# Qwiic_Quad_Relay.net
KiCad netlist of a schematic drawn in EAGLE
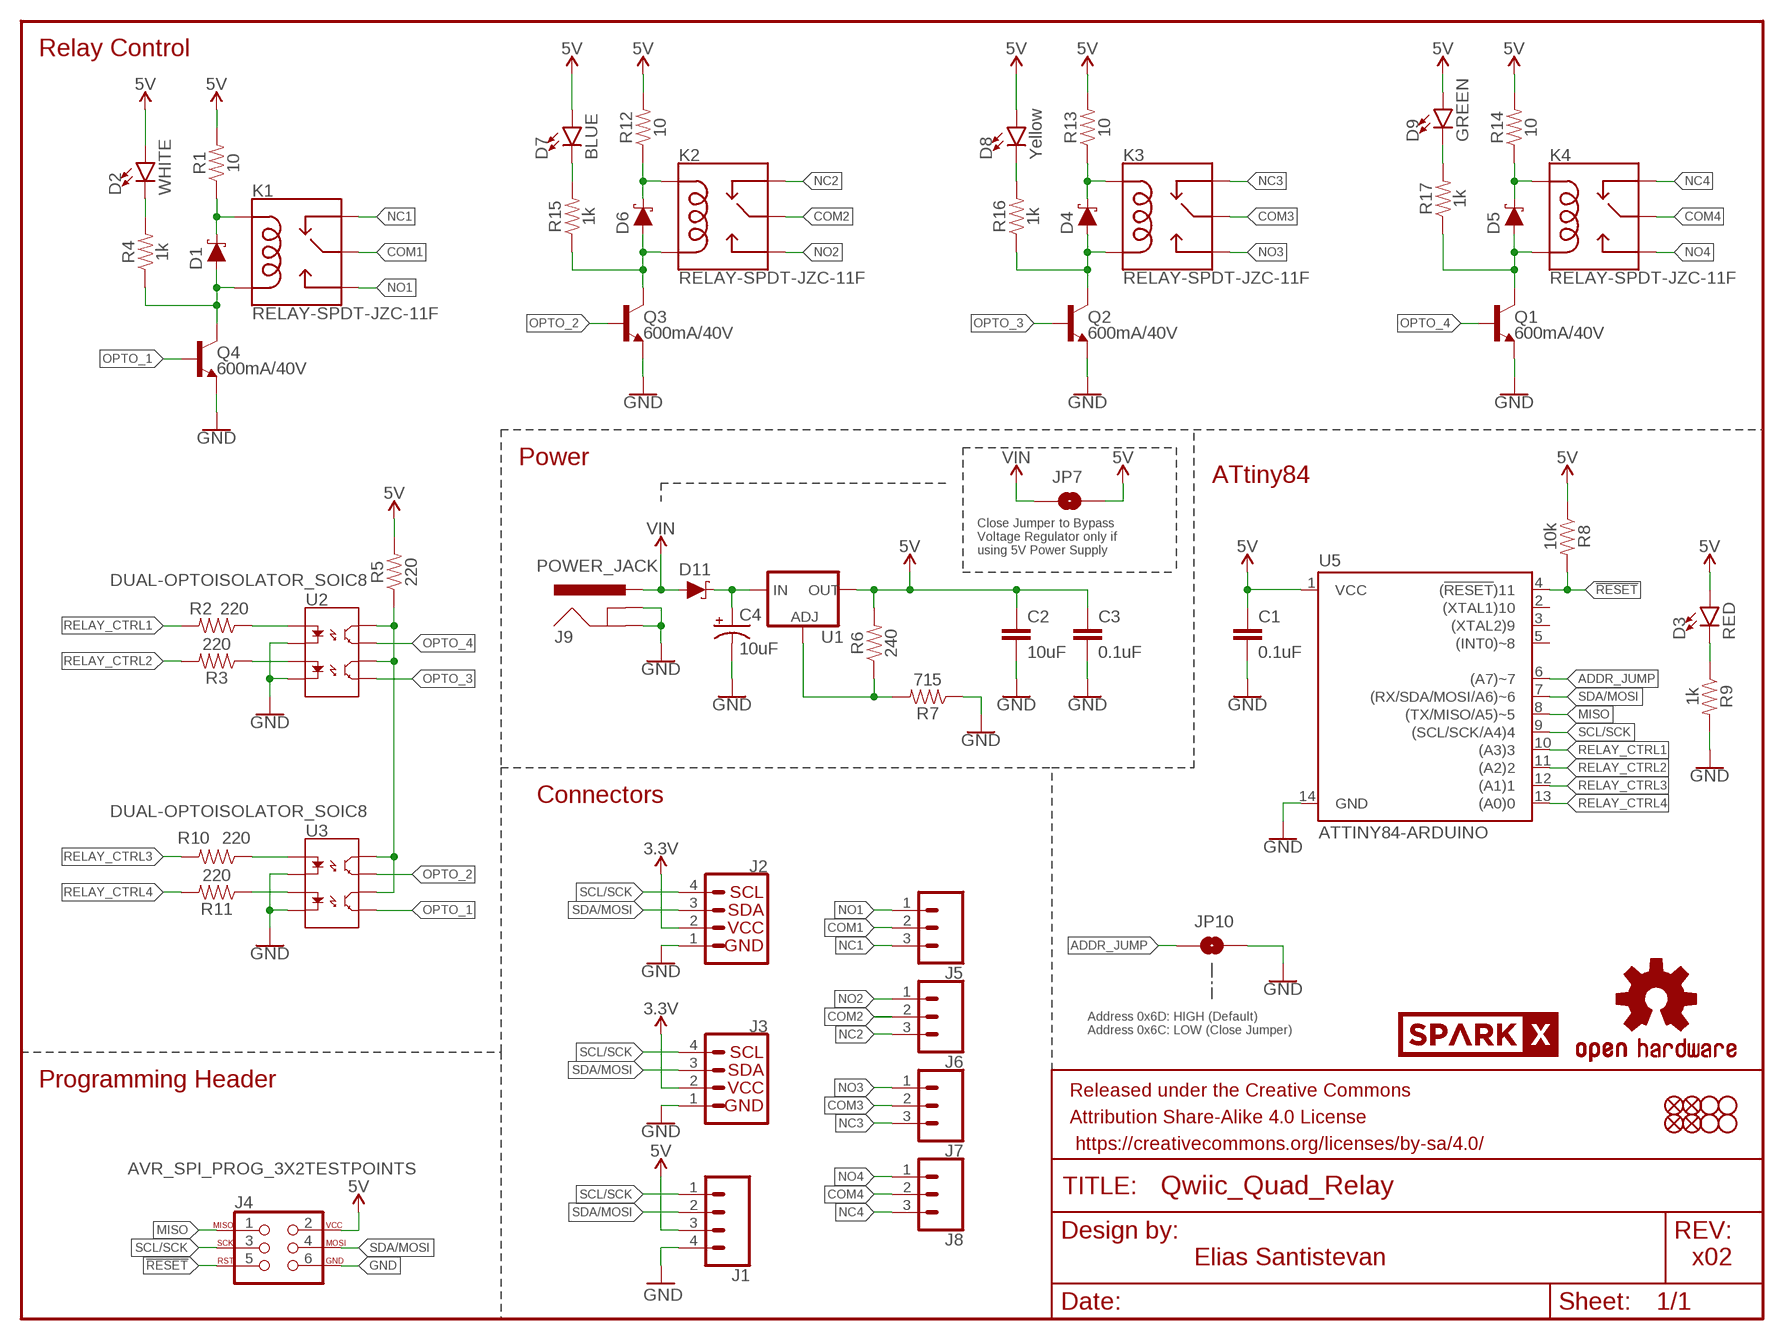
[diagram p0: schematic, sheet 1]

(export (version "E")
  (design (tool "Eeschema 10.0.6"))
  (components
    (comp (ref "C1")
      (value "0.1uF")
      (footprint "eagle-import:0603")
      (libsource (lib "eagle-import") (part "0.1UF-0603-25V-(+80/-20%)"))
    )
    (comp (ref "C2")
      (value "10uF")
      (footprint "eagle-import:0603")
      (libsource (lib "eagle-import") (part "10UF-0603-6.3V-20%"))
    )
    (comp (ref "C3")
      (value "0.1uF")
      (footprint "eagle-import:0603")
      (libsource (lib "eagle-import") (part "0.1UF-0603-25V-(+80/-20%)"))
    )
    (comp (ref "C4")
      (value "10uF")
      (footprint "eagle-import:EIA3528")
      (libsource (lib "eagle-import") (part "10UF-POLAR-EIA3528-20V-10%(TANT)"))
    )
    (comp (ref "D1")
      (value "1A/23V/620mV")
      (footprint "eagle-import:SOD-323")
      (libsource (lib "eagle-import") (part "DIODE-SCHOTTKY-BAT20J"))
    )
    (comp (ref "D2")
      (value "WHITE")
      (footprint "eagle-import:LED-0603")
      (libsource (lib "eagle-import") (part "LED-WHITE0603"))
    )
    (comp (ref "D3")
      (value "RED")
      (footprint "eagle-import:LED-0603")
      (libsource (lib "eagle-import") (part "LED-RED0603"))
    )
    (comp (ref "D4")
      (value "1A/23V/620mV")
      (footprint "eagle-import:SOD-323")
      (libsource (lib "eagle-import") (part "DIODE-SCHOTTKY-BAT20J"))
    )
    (comp (ref "D5")
      (value "1A/23V/620mV")
      (footprint "eagle-import:SOD-323")
      (libsource (lib "eagle-import") (part "DIODE-SCHOTTKY-BAT20J"))
    )
    (comp (ref "D6")
      (value "1A/23V/620mV")
      (footprint "eagle-import:SOD-323")
      (libsource (lib "eagle-import") (part "DIODE-SCHOTTKY-BAT20J"))
    )
    (comp (ref "D7")
      (value "BLUE")
      (footprint "eagle-import:LED-0603")
      (libsource (lib "eagle-import") (part "LED-BLUE0603"))
    )
    (comp (ref "D8")
      (value "Yellow")
      (footprint "eagle-import:LED-0603")
      (libsource (lib "eagle-import") (part "LED-YELLOW0603"))
    )
    (comp (ref "D9")
      (value "GREEN")
      (footprint "eagle-import:LED-0603")
      (libsource (lib "eagle-import") (part "LED-GREEN0603"))
    )
    (comp (ref "D11")
      (value "1A/40V/500mV")
      (footprint "eagle-import:SMA-DIODE")
      (libsource (lib "eagle-import") (part "DIODE-SCHOTTKY-SS14"))
    )
    (comp (ref "FRAME1")
      (value "FRAME-LETTER")
      (footprint "eagle-import:CREATIVE_COMMONS")
      (libsource (lib "eagle-import") (part "FRAME-LETTER"))
    )
    (comp (ref "J1")
      (value "CONN_041X04_NO_SILK")
      (footprint "eagle-import:1X04_NO_SILK")
      (libsource (lib "eagle-import") (part "CONN_041X04_NO_SILK"))
    )
    (comp (ref "J2")
      (value "Qwiic Right Angle")
      (footprint "eagle-import:1X04_1MM_RA")
      (libsource (lib "eagle-import") (part "I2C_STANDARDQWIIC"))
    )
    (comp (ref "J3")
      (value "Qwiic Right Angle")
      (footprint "eagle-import:1X04_1MM_RA")
      (libsource (lib "eagle-import") (part "I2C_STANDARDQWIIC"))
    )
    (comp (ref "J4")
      (value "AVR_SPI_PROG_3X2TESTPOINTS")
      (footprint "eagle-import:2X3_TEST_POINTS")
      (libsource (lib "eagle-import") (part "AVR_SPI_PROG_3X2TESTPOINTS"))
    )
    (comp (ref "J5")
      (value "CONN_03-SCREW-5MM")
      (footprint "eagle-import:SCREWTERMINAL-5MM-3")
      (libsource (lib "eagle-import") (part "CONN_03-SCREW-5MM"))
    )
    (comp (ref "J6")
      (value "CONN_03-SCREW-5MM")
      (footprint "eagle-import:SCREWTERMINAL-5MM-3")
      (libsource (lib "eagle-import") (part "CONN_03-SCREW-5MM"))
    )
    (comp (ref "J7")
      (value "CONN_03-SCREW-5MM")
      (footprint "eagle-import:SCREWTERMINAL-5MM-3")
      (libsource (lib "eagle-import") (part "CONN_03-SCREW-5MM"))
    )
    (comp (ref "J8")
      (value "CONN_03-SCREW-5MM")
      (footprint "eagle-import:SCREWTERMINAL-5MM-3")
      (libsource (lib "eagle-import") (part "CONN_03-SCREW-5MM"))
    )
    (comp (ref "J9")
      (value "POWER_JACK")
      (footprint "eagle-import:POWER_JACK_PTH")
      (libsource (lib "eagle-import") (part "POWER_JACK"))
    )
    (comp (ref "JP1")
      (value "STAND-OFF")
      (footprint "eagle-import:STAND-OFF")
      (libsource (lib "eagle-import") (part "STAND-OFF"))
    )
    (comp (ref "JP2")
      (value "FIDUCIAL1X2")
      (footprint "eagle-import:FIDUCIAL-1X2")
      (libsource (lib "eagle-import") (part "FIDUCIAL1X2"))
    )
    (comp (ref "JP3")
      (value "STAND-OFF")
      (footprint "eagle-import:STAND-OFF")
      (libsource (lib "eagle-import") (part "STAND-OFF"))
    )
    (comp (ref "JP4")
      (value "STAND-OFF")
      (footprint "eagle-import:STAND-OFF")
      (libsource (lib "eagle-import") (part "STAND-OFF"))
    )
    (comp (ref "JP5")
      (value "STAND-OFF")
      (footprint "eagle-import:STAND-OFF")
      (libsource (lib "eagle-import") (part "STAND-OFF"))
    )
    (comp (ref "JP6")
      (value "FIDUCIAL1X2")
      (footprint "eagle-import:FIDUCIAL-1X2")
      (libsource (lib "eagle-import") (part "FIDUCIAL1X2"))
    )
    (comp (ref "JP7")
      (value "JUMPER-SMT_2_NO_SILK")
      (footprint "eagle-import:SMT-JUMPER_2_NO_SILK")
      (libsource (lib "eagle-import") (part "JUMPER-SMT_2_NO_SILK"))
    )
    (comp (ref "JP8")
      (value "FIDUCIAL1X2")
      (footprint "eagle-import:FIDUCIAL-1X2")
      (libsource (lib "eagle-import") (part "FIDUCIAL1X2"))
    )
    (comp (ref "JP9")
      (value "FIDUCIAL1X2")
      (footprint "eagle-import:FIDUCIAL-1X2")
      (libsource (lib "eagle-import") (part "FIDUCIAL1X2"))
    )
    (comp (ref "JP10")
      (value "JUMPER-SMT_2_NO_SILK")
      (footprint "eagle-import:SMT-JUMPER_2_NO_SILK")
      (libsource (lib "eagle-import") (part "JUMPER-SMT_2_NO_SILK"))
    )
    (comp (ref "K1")
      (value "RELAY-SPDT-JZC-11F")
      (footprint "eagle-import:RELAY-JZC")
      (libsource (lib "eagle-import") (part "RELAY-SPDT-JZC-11F"))
    )
    (comp (ref "K2")
      (value "RELAY-SPDT-JZC-11F")
      (footprint "eagle-import:RELAY-JZC")
      (libsource (lib "eagle-import") (part "RELAY-SPDT-JZC-11F"))
    )
    (comp (ref "K3")
      (value "RELAY-SPDT-JZC-11F")
      (footprint "eagle-import:RELAY-JZC")
      (libsource (lib "eagle-import") (part "RELAY-SPDT-JZC-11F"))
    )
    (comp (ref "K4")
      (value "RELAY-SPDT-JZC-11F")
      (footprint "eagle-import:RELAY-JZC")
      (libsource (lib "eagle-import") (part "RELAY-SPDT-JZC-11F"))
    )
    (comp (ref "LOGO1")
      (value "OSHW-LOGOS")
      (footprint "eagle-import:OSHW-LOGO-S")
      (libsource (lib "eagle-import") (part "OSHW-LOGOS"))
    )
    (comp (ref "Q1")
      (value "600mA/40V")
      (footprint "eagle-import:SOT23-3")
      (libsource (lib "eagle-import") (part "TRANS_NPN-MMBT2222AL"))
    )
    (comp (ref "Q2")
      (value "600mA/40V")
      (footprint "eagle-import:SOT23-3")
      (libsource (lib "eagle-import") (part "TRANS_NPN-MMBT2222AL"))
    )
    (comp (ref "Q3")
      (value "600mA/40V")
      (footprint "eagle-import:SOT23-3")
      (libsource (lib "eagle-import") (part "TRANS_NPN-MMBT2222AL"))
    )
    (comp (ref "Q4")
      (value "600mA/40V")
      (footprint "eagle-import:SOT23-3")
      (libsource (lib "eagle-import") (part "TRANS_NPN-MMBT2222AL"))
    )
    (comp (ref "R1")
      (value "10")
      (footprint "eagle-import:0603")
      (libsource (lib "eagle-import") (part "10OHM-0603-1/10W-5%"))
    )
    (comp (ref "R2")
      (value "220")
      (footprint "eagle-import:0603")
      (libsource (lib "eagle-import") (part "220OHM-0603-1/10W-1%"))
    )
    (comp (ref "R3")
      (value "220")
      (footprint "eagle-import:0603")
      (libsource (lib "eagle-import") (part "220OHM-0603-1/10W-1%"))
    )
    (comp (ref "R4")
      (value "1k")
      (footprint "eagle-import:0603")
      (libsource (lib "eagle-import") (part "1KOHM-0603-1/10W-1%"))
    )
    (comp (ref "R5")
      (value "220")
      (footprint "eagle-import:0603")
      (libsource (lib "eagle-import") (part "220OHM-0603-1/10W-1%"))
    )
    (comp (ref "R6")
      (value "240")
      (footprint "eagle-import:0603")
      (libsource (lib "eagle-import") (part "240OHM-0603-1/10W-1%"))
    )
    (comp (ref "R7")
      (value "715")
      (footprint "eagle-import:0603")
      (libsource (lib "eagle-import") (part "715OHM-0603-1/10W-1%"))
    )
    (comp (ref "R8")
      (value "10k")
      (footprint "eagle-import:0603")
      (libsource (lib "eagle-import") (part "10KOHM-0603-1/10W-1%"))
    )
    (comp (ref "R9")
      (value "1k")
      (footprint "eagle-import:0603")
      (libsource (lib "eagle-import") (part "1KOHM-0603-1/10W-1%"))
    )
    (comp (ref "R10")
      (value "220")
      (footprint "eagle-import:0603")
      (libsource (lib "eagle-import") (part "220OHM-0603-1/10W-1%"))
    )
    (comp (ref "R11")
      (value "220")
      (footprint "eagle-import:0603")
      (libsource (lib "eagle-import") (part "220OHM-0603-1/10W-1%"))
    )
    (comp (ref "R12")
      (value "10")
      (footprint "eagle-import:0603")
      (libsource (lib "eagle-import") (part "10OHM-0603-1/10W-5%"))
    )
    (comp (ref "R13")
      (value "10")
      (footprint "eagle-import:0603")
      (libsource (lib "eagle-import") (part "10OHM-0603-1/10W-5%"))
    )
    (comp (ref "R14")
      (value "10")
      (footprint "eagle-import:0603")
      (libsource (lib "eagle-import") (part "10OHM-0603-1/10W-5%"))
    )
    (comp (ref "R15")
      (value "1k")
      (footprint "eagle-import:0603")
      (libsource (lib "eagle-import") (part "1KOHM-0603-1/10W-1%"))
    )
    (comp (ref "R16")
      (value "1k")
      (footprint "eagle-import:0603")
      (libsource (lib "eagle-import") (part "1KOHM-0603-1/10W-1%"))
    )
    (comp (ref "R17")
      (value "1k")
      (footprint "eagle-import:0603")
      (libsource (lib "eagle-import") (part "1KOHM-0603-1/10W-1%"))
    )
    (comp (ref "U$12")
      (value "SPARKX-LOGO4")
      (footprint "eagle-import:SPARKX-MEDIUM")
      (libsource (lib "eagle-import") (part "SPARKX-LOGO4"))
    )
    (comp (ref "U1")
      (value "V_REG_LM1117SOT223")
      (footprint "eagle-import:SOT223")
      (libsource (lib "eagle-import") (part "V_REG_LM1117SOT223"))
    )
    (comp (ref "U2")
      (value "DUAL-OPTOISOLATOR_SOIC8")
      (footprint "eagle-import:SO08")
      (libsource (lib "eagle-import") (part "DUAL-OPTOISOLATOR_SOIC8"))
    )
    (comp (ref "U3")
      (value "DUAL-OPTOISOLATOR_SOIC8")
      (footprint "eagle-import:SO08")
      (libsource (lib "eagle-import") (part "DUAL-OPTOISOLATOR_SOIC8"))
    )
    (comp (ref "U5")
      (value "ATTINY84-ARDUINO")
      (footprint "eagle-import:SO14")
      (libsource (lib "eagle-import") (part "ATTINY84-ARDUINO"))
    )
  )
  (nets
    (net (code "1") (name "/~{RESET}") (class "Default")
      (node (ref "J4") (pin "5") (pinfunction "5_5") (pintype "passive"))
      (node (ref "R8") (pin "2") (pinfunction "2_2") (pintype "passive"))
      (node (ref "U5") (pin "4") (pinfunction "(~{RESET})11_4") (pintype "bidirectional"))
    )
    (net (code "2") (name "3.3V") (class "Default")
      (node (ref "J2") (pin "2") (pinfunction "2_2") (pintype "power_in"))
      (node (ref "J3") (pin "2") (pinfunction "2_2") (pintype "power_in"))
    )
    (net (code "3") (name "5V") (class "Default")
      (node (ref "C1") (pin "1") (pinfunction "1_1") (pintype "passive"))
      (node (ref "C2") (pin "1") (pinfunction "1_1") (pintype "passive"))
      (node (ref "C3") (pin "1") (pinfunction "1_1") (pintype "passive"))
      (node (ref "D2") (pin "A") (pinfunction "A_A") (pintype "passive"))
      (node (ref "D3") (pin "A") (pinfunction "A_A") (pintype "passive"))
      (node (ref "D7") (pin "A") (pinfunction "A_A") (pintype "passive"))
      (node (ref "D8") (pin "A") (pinfunction "A_A") (pintype "passive"))
      (node (ref "D9") (pin "A") (pinfunction "A_A") (pintype "passive"))
      (node (ref "J1") (pin "3") (pinfunction "3_3") (pintype "passive"))
      (node (ref "J4") (pin "2") (pinfunction "2_2") (pintype "passive"))
      (node (ref "JP7") (pin "2") (pinfunction "2_2") (pintype "passive"))
      (node (ref "R1") (pin "2") (pinfunction "2_2") (pintype "passive"))
      (node (ref "R12") (pin "2") (pinfunction "2_2") (pintype "passive"))
      (node (ref "R13") (pin "2") (pinfunction "2_2") (pintype "passive"))
      (node (ref "R14") (pin "2") (pinfunction "2_2") (pintype "passive"))
      (node (ref "R5") (pin "2") (pinfunction "2_2") (pintype "passive"))
      (node (ref "R6") (pin "2") (pinfunction "2_2") (pintype "passive"))
      (node (ref "R8") (pin "1") (pinfunction "1_1") (pintype "passive"))
      (node (ref "U1") (pin "2") (pinfunction "OUT_2") (pintype "output"))
      (node (ref "U1") (pin "4") (pinfunction "OUT_4") (pintype "output"))
      (node (ref "U5") (pin "1") (pinfunction "VCC_1") (pintype "bidirectional"))
    )
    (net (code "4") (name "ADDR_JUMP") (class "Default")
      (node (ref "JP10") (pin "1") (pinfunction "1_1") (pintype "passive"))
      (node (ref "U5") (pin "6") (pinfunction "(A7)~{7}_6") (pintype "bidirectional"))
    )
    (net (code "5") (name "COM1") (class "Default")
      (node (ref "J5") (pin "2") (pinfunction "2_2") (pintype "passive"))
      (node (ref "K1") (pin "4") (pinfunction "MAIN_4") (pintype "bidirectional"))
    )
    (net (code "6") (name "COM2") (class "Default")
      (node (ref "J6") (pin "2") (pinfunction "2_2") (pintype "passive"))
      (node (ref "K2") (pin "4") (pinfunction "MAIN_4") (pintype "bidirectional"))
    )
    (net (code "7") (name "COM3") (class "Default")
      (node (ref "J7") (pin "2") (pinfunction "2_2") (pintype "passive"))
      (node (ref "K3") (pin "4") (pinfunction "MAIN_4") (pintype "bidirectional"))
    )
    (net (code "8") (name "COM4") (class "Default")
      (node (ref "J8") (pin "2") (pinfunction "2_2") (pintype "passive"))
      (node (ref "K4") (pin "4") (pinfunction "MAIN_4") (pintype "bidirectional"))
    )
    (net (code "9") (name "GND") (class "Default")
      (node (ref "C1") (pin "2") (pinfunction "2_2") (pintype "passive"))
      (node (ref "C2") (pin "2") (pinfunction "2_2") (pintype "passive"))
      (node (ref "C3") (pin "2") (pinfunction "2_2") (pintype "passive"))
      (node (ref "C4") (pin "C") (pinfunction "-_C") (pintype "passive"))
      (node (ref "J1") (pin "4") (pinfunction "4_4") (pintype "passive"))
      (node (ref "J2") (pin "1") (pinfunction "1_1") (pintype "power_in"))
      (node (ref "J3") (pin "1") (pinfunction "1_1") (pintype "power_in"))
      (node (ref "J4") (pin "6") (pinfunction "6_6") (pintype "passive"))
      (node (ref "J9") (pin "GND") (pinfunction "GND_GND") (pintype "bidirectional"))
      (node (ref "J9") (pin "GNDBREAK") (pinfunction "GNDBREAK_GNDBREAK") (pintype "bidirectional"))
      (node (ref "JP10") (pin "2") (pinfunction "2_2") (pintype "passive"))
      (node (ref "Q1") (pin "2") (pinfunction "E_2") (pintype "passive"))
      (node (ref "Q2") (pin "2") (pinfunction "E_2") (pintype "passive"))
      (node (ref "Q3") (pin "2") (pinfunction "E_2") (pintype "passive"))
      (node (ref "Q4") (pin "2") (pinfunction "E_2") (pintype "passive"))
      (node (ref "R7") (pin "1") (pinfunction "1_1") (pintype "passive"))
      (node (ref "R9") (pin "2") (pinfunction "2_2") (pintype "passive"))
      (node (ref "U2") (pin "2") (pinfunction "C1_2") (pintype "bidirectional"))
      (node (ref "U2") (pin "4") (pinfunction "C2_4") (pintype "bidirectional"))
      (node (ref "U3") (pin "2") (pinfunction "C1_2") (pintype "bidirectional"))
      (node (ref "U3") (pin "4") (pinfunction "C2_4") (pintype "bidirectional"))
      (node (ref "U5") (pin "14") (pinfunction "GND_14") (pintype "bidirectional"))
    )
    (net (code "10") (name "MISO") (class "Default")
      (node (ref "J4") (pin "1") (pinfunction "1_1") (pintype "passive"))
      (node (ref "U5") (pin "8") (pinfunction "(TX/MISO/A5)~{5}_8") (pintype "bidirectional"))
    )
    (net (code "11") (name "NC1") (class "Default")
      (node (ref "J5") (pin "3") (pinfunction "3_3") (pintype "passive"))
      (node (ref "K1") (pin "2") (pinfunction "NC_2") (pintype "bidirectional"))
    )
    (net (code "12") (name "NC2") (class "Default")
      (node (ref "J6") (pin "3") (pinfunction "3_3") (pintype "passive"))
      (node (ref "K2") (pin "2") (pinfunction "NC_2") (pintype "bidirectional"))
    )
    (net (code "13") (name "NC3") (class "Default")
      (node (ref "J7") (pin "3") (pinfunction "3_3") (pintype "passive"))
      (node (ref "K3") (pin "2") (pinfunction "NC_2") (pintype "bidirectional"))
    )
    (net (code "14") (name "NC4") (class "Default")
      (node (ref "J8") (pin "3") (pinfunction "3_3") (pintype "passive"))
      (node (ref "K4") (pin "2") (pinfunction "NC_2") (pintype "bidirectional"))
    )
    (net (code "15") (name "NO1") (class "Default")
      (node (ref "J5") (pin "1") (pinfunction "1_1") (pintype "passive"))
      (node (ref "K1") (pin "3") (pinfunction "NO_3") (pintype "bidirectional"))
    )
    (net (code "16") (name "NO2") (class "Default")
      (node (ref "J6") (pin "1") (pinfunction "1_1") (pintype "passive"))
      (node (ref "K2") (pin "3") (pinfunction "NO_3") (pintype "bidirectional"))
    )
    (net (code "17") (name "NO3") (class "Default")
      (node (ref "J7") (pin "1") (pinfunction "1_1") (pintype "passive"))
      (node (ref "K3") (pin "3") (pinfunction "NO_3") (pintype "bidirectional"))
    )
    (net (code "18") (name "NO4") (class "Default")
      (node (ref "J8") (pin "1") (pinfunction "1_1") (pintype "passive"))
      (node (ref "K4") (pin "3") (pinfunction "NO_3") (pintype "bidirectional"))
    )
    (net (code "19") (name "Net-(C4-+)") (class "Default")
      (node (ref "C4") (pin "A") (pinfunction "+_A") (pintype "passive"))
      (node (ref "D11") (pin "C") (pinfunction "C_C") (pintype "passive"))
      (node (ref "U1") (pin "3") (pinfunction "IN_3") (pintype "input"))
    )
    (net (code "20") (name "Net-(D2-PadC)") (class "Default")
      (node (ref "D2") (pin "C") (pinfunction "C_C") (pintype "passive"))
      (node (ref "R4") (pin "2") (pinfunction "2_2") (pintype "passive"))
    )
    (net (code "21") (name "Net-(D3-PadC)") (class "Default")
      (node (ref "D3") (pin "C") (pinfunction "C_C") (pintype "passive"))
      (node (ref "R9") (pin "1") (pinfunction "1_1") (pintype "passive"))
    )
    (net (code "22") (name "Net-(D7-PadC)") (class "Default")
      (node (ref "D7") (pin "C") (pinfunction "C_C") (pintype "passive"))
      (node (ref "R15") (pin "2") (pinfunction "2_2") (pintype "passive"))
    )
    (net (code "23") (name "Net-(D8-PadC)") (class "Default")
      (node (ref "D8") (pin "C") (pinfunction "C_C") (pintype "passive"))
      (node (ref "R16") (pin "2") (pinfunction "2_2") (pintype "passive"))
    )
    (net (code "24") (name "Net-(D9-PadC)") (class "Default")
      (node (ref "D9") (pin "C") (pinfunction "C_C") (pintype "passive"))
      (node (ref "R17") (pin "2") (pinfunction "2_2") (pintype "passive"))
    )
    (net (code "25") (name "Net-(K1-COIL1)") (class "Default")
      (node (ref "D1") (pin "C") (pinfunction "C_C") (pintype "passive"))
      (node (ref "K1") (pin "5") (pinfunction "COIL1_5") (pintype "bidirectional"))
      (node (ref "R1") (pin "1") (pinfunction "1_1") (pintype "passive"))
    )
    (net (code "26") (name "Net-(K1-COIL2)") (class "Default")
      (node (ref "D1") (pin "A") (pinfunction "A_A") (pintype "passive"))
      (node (ref "K1") (pin "1") (pinfunction "COIL2_1") (pintype "bidirectional"))
      (node (ref "Q4") (pin "3") (pinfunction "C_3") (pintype "passive"))
      (node (ref "R4") (pin "1") (pinfunction "1_1") (pintype "passive"))
    )
    (net (code "27") (name "Net-(K2-COIL1)") (class "Default")
      (node (ref "D6") (pin "C") (pinfunction "C_C") (pintype "passive"))
      (node (ref "K2") (pin "5") (pinfunction "COIL1_5") (pintype "bidirectional"))
      (node (ref "R12") (pin "1") (pinfunction "1_1") (pintype "passive"))
    )
    (net (code "28") (name "Net-(K2-COIL2)") (class "Default")
      (node (ref "D6") (pin "A") (pinfunction "A_A") (pintype "passive"))
      (node (ref "K2") (pin "1") (pinfunction "COIL2_1") (pintype "bidirectional"))
      (node (ref "Q3") (pin "3") (pinfunction "C_3") (pintype "passive"))
      (node (ref "R15") (pin "1") (pinfunction "1_1") (pintype "passive"))
    )
    (net (code "29") (name "Net-(K3-COIL1)") (class "Default")
      (node (ref "D4") (pin "C") (pinfunction "C_C") (pintype "passive"))
      (node (ref "K3") (pin "5") (pinfunction "COIL1_5") (pintype "bidirectional"))
      (node (ref "R13") (pin "1") (pinfunction "1_1") (pintype "passive"))
    )
    (net (code "30") (name "Net-(K3-COIL2)") (class "Default")
      (node (ref "D4") (pin "A") (pinfunction "A_A") (pintype "passive"))
      (node (ref "K3") (pin "1") (pinfunction "COIL2_1") (pintype "bidirectional"))
      (node (ref "Q2") (pin "3") (pinfunction "C_3") (pintype "passive"))
      (node (ref "R16") (pin "1") (pinfunction "1_1") (pintype "passive"))
    )
    (net (code "31") (name "Net-(K4-COIL1)") (class "Default")
      (node (ref "D5") (pin "C") (pinfunction "C_C") (pintype "passive"))
      (node (ref "K4") (pin "5") (pinfunction "COIL1_5") (pintype "bidirectional"))
      (node (ref "R14") (pin "1") (pinfunction "1_1") (pintype "passive"))
    )
    (net (code "32") (name "Net-(K4-COIL2)") (class "Default")
      (node (ref "D5") (pin "A") (pinfunction "A_A") (pintype "passive"))
      (node (ref "K4") (pin "1") (pinfunction "COIL2_1") (pintype "bidirectional"))
      (node (ref "Q1") (pin "3") (pinfunction "C_3") (pintype "passive"))
      (node (ref "R17") (pin "1") (pinfunction "1_1") (pintype "passive"))
    )
    (net (code "33") (name "Net-(U1-ADJ)") (class "Default")
      (node (ref "R6") (pin "1") (pinfunction "1_1") (pintype "passive"))
      (node (ref "R7") (pin "2") (pinfunction "2_2") (pintype "passive"))
      (node (ref "U1") (pin "1") (pinfunction "ADJ_1") (pintype "input"))
    )
    (net (code "34") (name "Net-(U2-A1)") (class "Default")
      (node (ref "R2") (pin "1") (pinfunction "1_1") (pintype "passive"))
      (node (ref "U2") (pin "1") (pinfunction "A1_1") (pintype "bidirectional"))
    )
    (net (code "35") (name "Net-(U2-A2)") (class "Default")
      (node (ref "R3") (pin "1") (pinfunction "1_1") (pintype "passive"))
      (node (ref "U2") (pin "3") (pinfunction "A2_3") (pintype "bidirectional"))
    )
    (net (code "36") (name "Net-(U2-CL1)") (class "Default")
      (node (ref "R5") (pin "1") (pinfunction "1_1") (pintype "passive"))
      (node (ref "U2") (pin "6") (pinfunction "CL2_6") (pintype "bidirectional"))
      (node (ref "U2") (pin "8") (pinfunction "CL1_8") (pintype "bidirectional"))
      (node (ref "U3") (pin "6") (pinfunction "CL2_6") (pintype "bidirectional"))
      (node (ref "U3") (pin "8") (pinfunction "CL1_8") (pintype "bidirectional"))
    )
    (net (code "37") (name "Net-(U3-A1)") (class "Default")
      (node (ref "R10") (pin "1") (pinfunction "1_1") (pintype "passive"))
      (node (ref "U3") (pin "1") (pinfunction "A1_1") (pintype "bidirectional"))
    )
    (net (code "38") (name "Net-(U3-A2)") (class "Default")
      (node (ref "R11") (pin "1") (pinfunction "1_1") (pintype "passive"))
      (node (ref "U3") (pin "3") (pinfunction "A2_3") (pintype "bidirectional"))
    )
    (net (code "39") (name "OPTO_1") (class "Default")
      (node (ref "Q4") (pin "1") (pinfunction "B_1") (pintype "passive"))
      (node (ref "U3") (pin "5") (pinfunction "EM2_5") (pintype "bidirectional"))
    )
    (net (code "40") (name "OPTO_2") (class "Default")
      (node (ref "Q3") (pin "1") (pinfunction "B_1") (pintype "passive"))
      (node (ref "U3") (pin "7") (pinfunction "EM1_7") (pintype "bidirectional"))
    )
    (net (code "41") (name "OPTO_3") (class "Default")
      (node (ref "Q2") (pin "1") (pinfunction "B_1") (pintype "passive"))
      (node (ref "U2") (pin "5") (pinfunction "EM2_5") (pintype "bidirectional"))
    )
    (net (code "42") (name "OPTO_4") (class "Default")
      (node (ref "Q1") (pin "1") (pinfunction "B_1") (pintype "passive"))
      (node (ref "U2") (pin "7") (pinfunction "EM1_7") (pintype "bidirectional"))
    )
    (net (code "43") (name "RELAY_CTRL1") (class "Default")
      (node (ref "R2") (pin "2") (pinfunction "2_2") (pintype "passive"))
      (node (ref "U5") (pin "10") (pinfunction "(A3)3_10") (pintype "bidirectional"))
    )
    (net (code "44") (name "RELAY_CTRL2") (class "Default")
      (node (ref "R3") (pin "2") (pinfunction "2_2") (pintype "passive"))
      (node (ref "U5") (pin "11") (pinfunction "(A2)2_11") (pintype "bidirectional"))
    )
    (net (code "45") (name "RELAY_CTRL3") (class "Default")
      (node (ref "R10") (pin "2") (pinfunction "2_2") (pintype "passive"))
      (node (ref "U5") (pin "12") (pinfunction "(A1)1_12") (pintype "bidirectional"))
    )
    (net (code "46") (name "RELAY_CTRL4") (class "Default")
      (node (ref "R11") (pin "2") (pinfunction "2_2") (pintype "passive"))
      (node (ref "U5") (pin "13") (pinfunction "(A0)0_13") (pintype "bidirectional"))
    )
    (net (code "47") (name "SCL{slash}SCK") (class "Default")
      (node (ref "J1") (pin "1") (pinfunction "1_1") (pintype "passive"))
      (node (ref "J2") (pin "4") (pinfunction "4_4") (pintype "passive"))
      (node (ref "J3") (pin "4") (pinfunction "4_4") (pintype "passive"))
      (node (ref "J4") (pin "3") (pinfunction "3_3") (pintype "passive"))
      (node (ref "U5") (pin "9") (pinfunction "(SCL/SCK/A4)4_9") (pintype "bidirectional"))
    )
    (net (code "48") (name "SDA{slash}MOSI") (class "Default")
      (node (ref "J1") (pin "2") (pinfunction "2_2") (pintype "passive"))
      (node (ref "J2") (pin "3") (pinfunction "3_3") (pintype "passive"))
      (node (ref "J3") (pin "3") (pinfunction "3_3") (pintype "passive"))
      (node (ref "J4") (pin "4") (pinfunction "4_4") (pintype "passive"))
      (node (ref "U5") (pin "7") (pinfunction "(RX/SDA/MOSI/A6)~{6}_7") (pintype "bidirectional"))
    )
    (net (code "49") (name "VIN") (class "Default")
      (node (ref "D11") (pin "A") (pinfunction "A_A") (pintype "passive"))
      (node (ref "J9") (pin "PWR") (pinfunction "PWR_PWR") (pintype "bidirectional"))
      (node (ref "JP7") (pin "1") (pinfunction "1_1") (pintype "passive"))
    )
    (net (code "50") (name "unconnected-(U5-(INT0)~{8}-Pad5)") (class "Default")
      (node (ref "U5") (pin "5") (pinfunction "(INT0)~{8}_5") (pintype "bidirectional"))
    )
    (net (code "51") (name "unconnected-(U5-(XTAL1)10-Pad2)") (class "Default")
      (node (ref "U5") (pin "2") (pinfunction "(XTAL1)10_2") (pintype "bidirectional"))
    )
    (net (code "52") (name "unconnected-(U5-(XTAL2)9-Pad3)") (class "Default")
      (node (ref "U5") (pin "3") (pinfunction "(XTAL2)9_3") (pintype "bidirectional"))
    )
  )
)
